# OpenBook_Schematic_v61.net
KiCad netlist of a schematic drawn in EAGLE
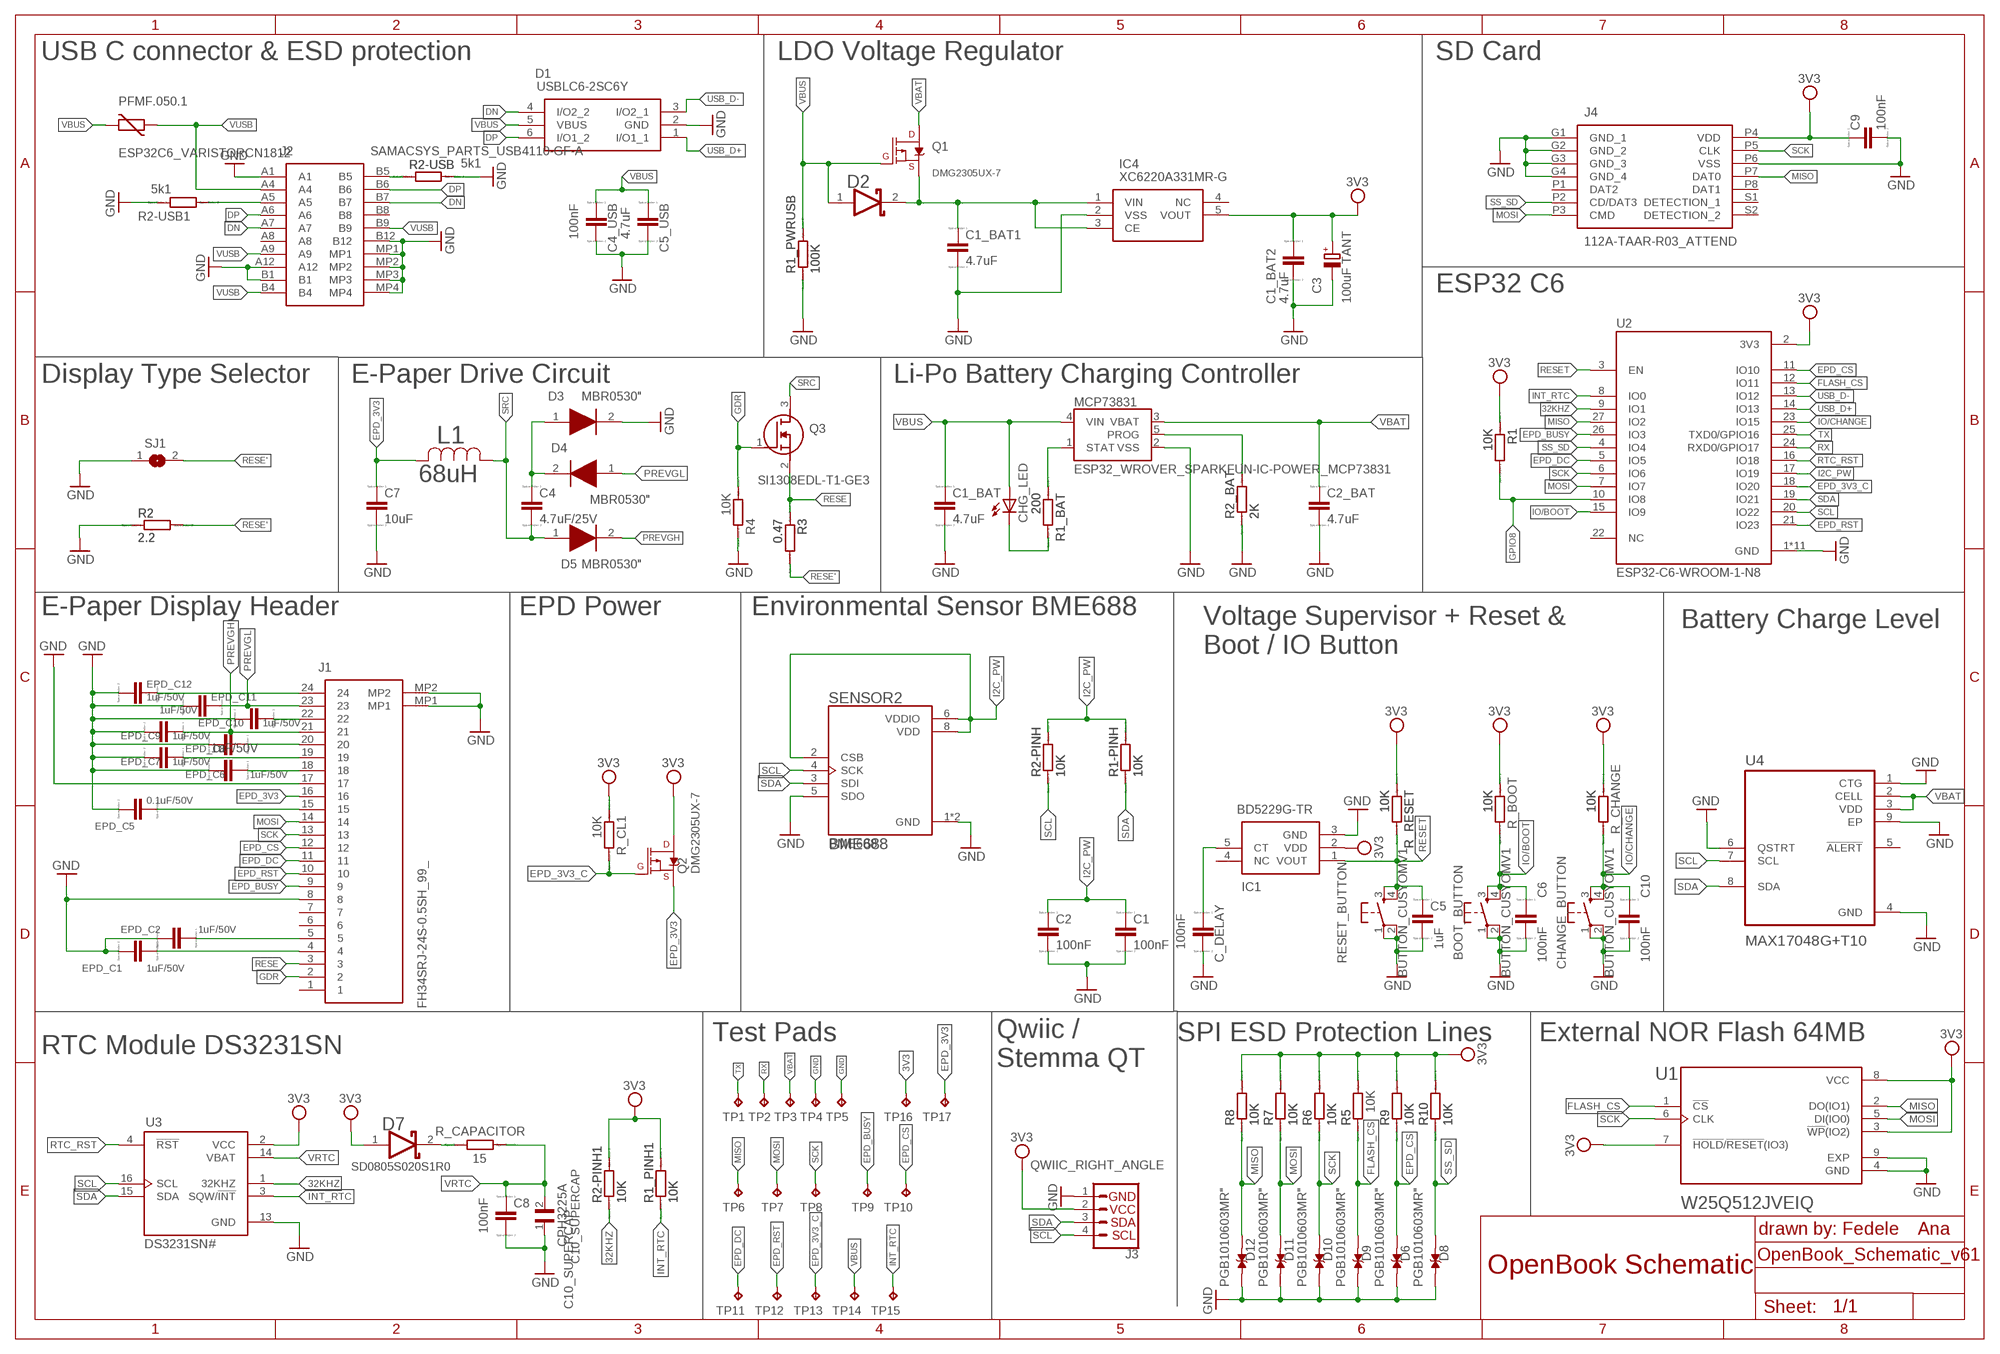
[diagram p0: schematic, sheet 1]

(export (version "E")
  (design (tool "Eeschema 10.0.6"))
  (components
    (comp (ref "BOOT_BUTTON")
      (value "BUTTON_CUSYOMV1")
      (footprint "eagle-import:MYBUTTON")
      (libsource (lib "eagle-import") (part "BUTTON_CUSYOMV1"))
    )
    (comp (ref "C1")
      (value "100nF")
      (footprint "eagle-import:ESP32_WROVER_EAGLE-LTSPICE_C0402")
      (libsource (lib "eagle-import") (part "ESP32_WROVER_EAGLE-LTSPICE_CC0402"))
    )
    (comp (ref "C1_BAT")
      (value "4.7uF")
      (footprint "eagle-import:ESP32_WROVER_EAGLE-LTSPICE_C0402")
      (libsource (lib "eagle-import") (part "ESP32_WROVER_EAGLE-LTSPICE_CC0402"))
    )
    (comp (ref "C1_BAT1")
      (value "4.7uF")
      (footprint "eagle-import:ESP32_WROVER_EAGLE-LTSPICE_C0402")
      (libsource (lib "eagle-import") (part "ESP32_WROVER_EAGLE-LTSPICE_CC0402"))
    )
    (comp (ref "C1_BAT2")
      (value "4.7uF")
      (footprint "eagle-import:ESP32_WROVER_EAGLE-LTSPICE_C0402")
      (libsource (lib "eagle-import") (part "ESP32_WROVER_EAGLE-LTSPICE_CC0402"))
    )
    (comp (ref "C2")
      (value "100nF")
      (footprint "eagle-import:ESP32_WROVER_EAGLE-LTSPICE_C0402")
      (libsource (lib "eagle-import") (part "ESP32_WROVER_EAGLE-LTSPICE_CC0402"))
    )
    (comp (ref "C2_BAT")
      (value "4.7uF")
      (footprint "eagle-import:ESP32_WROVER_EAGLE-LTSPICE_C0402")
      (libsource (lib "eagle-import") (part "ESP32_WROVER_EAGLE-LTSPICE_CC0402"))
    )
    (comp (ref "C3")
      (value "100uF TANT")
      (footprint "eagle-import:RCL_CT3528")
      (libsource (lib "eagle-import") (part "RCL_CPOL-EUCT3528"))
    )
    (comp (ref "C4")
      (value "4.7uF/25V")
      (footprint "eagle-import:ESP32_WROVER_EAGLE-LTSPICE_C0402")
      (libsource (lib "eagle-import") (part "ESP32_WROVER_EAGLE-LTSPICE_CC0402"))
    )
    (comp (ref "C4_USB")
      (value "100nF")
      (footprint "eagle-import:ESP32_WROVER_EAGLE-LTSPICE_C0402")
      (libsource (lib "eagle-import") (part "ESP32_WROVER_EAGLE-LTSPICE_CC0402"))
    )
    (comp (ref "C5")
      (value "1uF")
      (footprint "eagle-import:ESP32_WROVER_EAGLE-LTSPICE_C0402")
      (libsource (lib "eagle-import") (part "ESP32_WROVER_EAGLE-LTSPICE_CC0402"))
    )
    (comp (ref "C5_USB")
      (value "4.7uF")
      (footprint "eagle-import:ESP32_WROVER_EAGLE-LTSPICE_C0402")
      (libsource (lib "eagle-import") (part "ESP32_WROVER_EAGLE-LTSPICE_CC0402"))
    )
    (comp (ref "C6")
      (value "100nF")
      (footprint "eagle-import:ESP32_WROVER_EAGLE-LTSPICE_C0402")
      (libsource (lib "eagle-import") (part "ESP32_WROVER_EAGLE-LTSPICE_CC0402"))
    )
    (comp (ref "C7")
      (value "10uF")
      (footprint "eagle-import:ESP32_WROVER_EAGLE-LTSPICE_C0402")
      (libsource (lib "eagle-import") (part "ESP32_WROVER_EAGLE-LTSPICE_CC0402"))
    )
    (comp (ref "C8")
      (value "100nF")
      (footprint "eagle-import:ESP32_WROVER_EAGLE-LTSPICE_C0402")
      (libsource (lib "eagle-import") (part "ESP32_WROVER_EAGLE-LTSPICE_CC0402"))
    )
    (comp (ref "C9")
      (value "100nF")
      (footprint "eagle-import:ESP32_WROVER_EAGLE-LTSPICE_C0402")
      (libsource (lib "eagle-import") (part "ESP32_WROVER_EAGLE-LTSPICE_CC0402"))
    )
    (comp (ref "C10")
      (value "100nF")
      (footprint "eagle-import:ESP32_WROVER_EAGLE-LTSPICE_C0402")
      (libsource (lib "eagle-import") (part "ESP32_WROVER_EAGLE-LTSPICE_CC0402"))
    )
    (comp (ref "C10_SUPERCAP")
      (value "CPH3225A")
      (footprint "eagle-import:CAPCP3225X100N")
      (fields (field (name "MF") "Seiko Instruments"))
      (libsource (lib "eagle-import") (part "CPH3225A"))
    )
    (comp (ref "CHANGE_BUTTON")
      (value "BUTTON_CUSYOMV1")
      (footprint "eagle-import:MYBUTTON")
      (libsource (lib "eagle-import") (part "BUTTON_CUSYOMV1"))
    )
    (comp (ref "CHG_LED")
      (value "ADAFRUIT_LEDCHIP-LED0603")
      (footprint "eagle-import:ADAFRUIT_CHIP-LED0603")
      (libsource (lib "eagle-import") (part "ADAFRUIT_LEDCHIP-LED0603"))
    )
    (comp (ref "C_DELAY")
      (value "100nF")
      (footprint "eagle-import:ESP32_WROVER_EAGLE-LTSPICE_C0402")
      (libsource (lib "eagle-import") (part "ESP32_WROVER_EAGLE-LTSPICE_CC0402"))
    )
    (comp (ref "D1")
      (value "USBLC6-2SC6Y")
      (footprint "eagle-import:SOT95P280X145-6N")
      (fields (field (name "MF") "STMicroelectronics"))
      (libsource (lib "eagle-import") (part "USBLC6-2SC6Y"))
    )
    (comp (ref "D2")
      (value "ESP32_WROVER_AVX---SD0805S020S1R0_AVX_SD0805S020S1R0_0_0AVX_SD0805S020S1R0_0_0")
      (footprint "eagle-import:ESP32_WROVER_AVX---SD0805S020S1R0_AVX_SD0805S020S1R0_0")
      (libsource (lib "eagle-import") (part "ESP32_WROVER_AVX---SD0805S020S1R0_AVX_SD0805S020S1R0_0_0AVX_SD0805S020S1R0_0_0"))
    )
    (comp (ref "D3")
      (value "MBR0530\"")
      (footprint "eagle-import:SOD3716X135N")
      (libsource (lib "eagle-import") (part "MBR0530{dblquote}"))
    )
    (comp (ref "D4")
      (value "MBR0530\"")
      (footprint "eagle-import:SOD3716X135N")
      (libsource (lib "eagle-import") (part "MBR0530{dblquote}"))
    )
    (comp (ref "D5")
      (value "MBR0530\"")
      (footprint "eagle-import:SOD3716X135N")
      (libsource (lib "eagle-import") (part "MBR0530{dblquote}"))
    )
    (comp (ref "D6")
      (value "PGB1010603MR\"")
      (footprint "eagle-import:DIOC1608X36N")
      (libsource (lib "eagle-import") (part "PGB1010603MR{dblquote}"))
    )
    (comp (ref "D7")
      (value "SD0805S020S1R0")
      (footprint "eagle-import:ESP32_WROVER_AVX---SD0805S020S1R0_AVX_SD0805S020S1R0_0")
      (libsource (lib "eagle-import") (part "ESP32_WROVER_AVX---SD0805S020S1R0_AVX_SD0805S020S1R0_0_0AVX_SD0805S020S1R0_0_0"))
    )
    (comp (ref "D8")
      (value "PGB1010603MR\"")
      (footprint "eagle-import:DIOC1608X36N")
      (libsource (lib "eagle-import") (part "PGB1010603MR{dblquote}"))
    )
    (comp (ref "D9")
      (value "PGB1010603MR\"")
      (footprint "eagle-import:DIOC1608X36N")
      (libsource (lib "eagle-import") (part "PGB1010603MR{dblquote}"))
    )
    (comp (ref "D10")
      (value "PGB1010603MR\"")
      (footprint "eagle-import:DIOC1608X36N")
      (libsource (lib "eagle-import") (part "PGB1010603MR{dblquote}"))
    )
    (comp (ref "D11")
      (value "PGB1010603MR\"")
      (footprint "eagle-import:DIOC1608X36N")
      (libsource (lib "eagle-import") (part "PGB1010603MR{dblquote}"))
    )
    (comp (ref "D12")
      (value "PGB1010603MR\"")
      (footprint "eagle-import:DIOC1608X36N")
      (libsource (lib "eagle-import") (part "PGB1010603MR{dblquote}"))
    )
    (comp (ref "EPD_C1")
      (value "1uF/50V")
      (footprint "eagle-import:ESP32_WROVER_EAGLE-LTSPICE_C0402")
      (libsource (lib "eagle-import") (part "ESP32_WROVER_EAGLE-LTSPICE_CC0402"))
    )
    (comp (ref "EPD_C2")
      (value "1uF/50V")
      (footprint "eagle-import:ESP32_WROVER_EAGLE-LTSPICE_C0402")
      (libsource (lib "eagle-import") (part "ESP32_WROVER_EAGLE-LTSPICE_CC0402"))
    )
    (comp (ref "EPD_C5")
      (value "0.1uF/50V")
      (footprint "eagle-import:ESP32_WROVER_EAGLE-LTSPICE_C0402")
      (libsource (lib "eagle-import") (part "ESP32_WROVER_EAGLE-LTSPICE_CC0402"))
    )
    (comp (ref "EPD_C6")
      (value "1uF/50V")
      (footprint "eagle-import:ESP32_WROVER_EAGLE-LTSPICE_C0402")
      (libsource (lib "eagle-import") (part "ESP32_WROVER_EAGLE-LTSPICE_CC0402"))
    )
    (comp (ref "EPD_C7")
      (value "1uF/50V")
      (footprint "eagle-import:ESP32_WROVER_EAGLE-LTSPICE_C0402")
      (libsource (lib "eagle-import") (part "ESP32_WROVER_EAGLE-LTSPICE_CC0402"))
    )
    (comp (ref "EPD_C8")
      (value "1uF/50V")
      (footprint "eagle-import:ESP32_WROVER_EAGLE-LTSPICE_C0402")
      (libsource (lib "eagle-import") (part "ESP32_WROVER_EAGLE-LTSPICE_CC0402"))
    )
    (comp (ref "EPD_C9")
      (value "1uF/50V")
      (footprint "eagle-import:ESP32_WROVER_EAGLE-LTSPICE_C0402")
      (libsource (lib "eagle-import") (part "ESP32_WROVER_EAGLE-LTSPICE_CC0402"))
    )
    (comp (ref "EPD_C10")
      (value "1uF/50V")
      (footprint "eagle-import:ESP32_WROVER_EAGLE-LTSPICE_C0402")
      (libsource (lib "eagle-import") (part "ESP32_WROVER_EAGLE-LTSPICE_CC0402"))
    )
    (comp (ref "EPD_C11")
      (value "1uF/50V")
      (footprint "eagle-import:ESP32_WROVER_EAGLE-LTSPICE_C0402")
      (libsource (lib "eagle-import") (part "ESP32_WROVER_EAGLE-LTSPICE_CC0402"))
    )
    (comp (ref "EPD_C12")
      (value "1uF/50V")
      (footprint "eagle-import:ESP32_WROVER_EAGLE-LTSPICE_C0402")
      (libsource (lib "eagle-import") (part "ESP32_WROVER_EAGLE-LTSPICE_CC0402"))
    )
    (comp (ref "IC1")
      (value "BD5229G-TR")
      (footprint "eagle-import:SOT95P280X125-5N")
      (fields (field (name "MOUSER_PART_NUMBER") "755-BD5229G-TR"))
      (libsource (lib "eagle-import") (part "BD5229G-TR"))
    )
    (comp (ref "IC4")
      (value "XC6220A331MR-G")
      (footprint "eagle-import:SOT95P280X120-5N")
      (fields (field (name "MOUSER_PART_NUMBER") "865-XC6220A331MR-G"))
      (libsource (lib "eagle-import") (part "XC6220A331MR-G"))
    )
    (comp (ref "J1")
      (value "FH34SRJ-24S-0.5SH_99_")
      (footprint "eagle-import:FH34SRJ24S05SH99")
      (fields
        (field (name "MANUFACTURER_PART_NUMBER") "FH34SRJ-24S-0.5SH(99)")
        (field (name "MOUSER_PART_NUMBER") "798-FH34SRJ24S05SH99")
      )
      (libsource (lib "eagle-import") (part "FH34SRJ-24S-0.5SH_99_"))
    )
    (comp (ref "J2")
      (value "SAMACSYS_PARTS_USB4110-GF-A")
      (footprint "eagle-import:SAMACSYS_PARTS_USB4110GFA")
      (fields
        (field (name "MANUFACTURER_PART_NUMBER") "USB4110-GF-A")
        (field (name "MOUSER_PART_NUMBER") "640-USB4110-GF-A")
      )
      (libsource (lib "eagle-import") (part "SAMACSYS_PARTS_USB4110-GF-A"))
    )
    (comp (ref "J3")
      (value "QWIIC_RIGHT_ANGLE")
      (footprint "eagle-import:JST04_1MM_RA")
      (libsource (lib "eagle-import") (part "QWIIC_CONNECTORJS-1MM"))
    )
    (comp (ref "J4")
      (value "112A-TAAR-R03_ATTEND")
      (footprint "eagle-import:112ATAARR03ATTEND")
      (fields (field (name "MANUFACTURER_PART_NUMBER") "112A-TAAR-R03 ATTEND"))
      (libsource (lib "eagle-import") (part "112A-TAAR-R03_ATTEND"))
    )
    (comp (ref "L1")
      (value "68uH")
      (footprint "eagle-import:IND_4828-WE-TPC_WRE")
      (fields
        (field (name "MANUFACTURER_PART_NUMBER") "744043680")
        (field (name "COPYRIGHT") "Copyright (C) 2024 Ultra Librarian. All rights reserved.")
      )
      (libsource (lib "eagle-import") (part "744043680IND_4828-WE-TPC_WRE"))
    )
    (comp (ref "MCP73831")
      (value "ESP32_WROVER_SPARKFUN-IC-POWER_MCP73831")
      (footprint "eagle-import:ESP32_WROVER_SPARKFUN-IC-POWER_SOT23-5")
      (libsource (lib "eagle-import") (part "ESP32_WROVER_SPARKFUN-IC-POWER_MCP73831"))
    )
    (comp (ref "PFMF.050.1")
      (value "ESP32C6_VARISTORCN1812")
      (footprint "eagle-import:ESP32C6_VARISTOR_CT_CN1812")
      (libsource (lib "eagle-import") (part "ESP32C6_VARISTORCN1812"))
    )
    (comp (ref "Q1")
      (value "20V/4.2A/52mΩ/1.4W")
      (footprint "eagle-import:ESP32_WROVER_SPARKFUN-DISCRETESEMI_SOT23-3")
      (libsource (lib "eagle-import") (part "ESP32_WROVER_SPARKFUN-DISCRETESEMI_MOSFET_PCH-DMG2305UX-7"))
    )
    (comp (ref "Q2")
      (value "20V/4.2A/52mΩ/1.4W")
      (footprint "eagle-import:ESP32_WROVER_SPARKFUN-DISCRETESEMI_SOT23-3")
      (libsource (lib "eagle-import") (part "ESP32_WROVER_SPARKFUN-DISCRETESEMI_MOSFET_PCH-DMG2305UX-7"))
    )
    (comp (ref "Q3")
      (value "SI1308EDL-T1-GE3")
      (footprint "eagle-import:SOT65P210X110-3N")
      (fields (field (name "MF") "Vishay Siliconix"))
      (libsource (lib "eagle-import") (part "SI1308EDL-T1-GE3"))
    )
    (comp (ref "R1")
      (value "10K")
      (footprint "eagle-import:ESP32_WROVER_EAGLE-LTSPICE_R0402")
      (libsource (lib "eagle-import") (part "ESP32_WROVER_EAGLE-LTSPICE_RR0402"))
    )
    (comp (ref "R1-PINH")
      (value "10K")
      (footprint "eagle-import:ESP32_WROVER_EAGLE-LTSPICE_R0402")
      (libsource (lib "eagle-import") (part "ESP32_WROVER_EAGLE-LTSPICE_RR0402"))
    )
    (comp (ref "R1_BAT")
      (value "200")
      (footprint "eagle-import:ESP32_WROVER_EAGLE-LTSPICE_R0402")
      (libsource (lib "eagle-import") (part "ESP32_WROVER_EAGLE-LTSPICE_RR0402"))
    )
    (comp (ref "R1_PINH1")
      (value "10K")
      (footprint "eagle-import:ESP32_WROVER_EAGLE-LTSPICE_R0402")
      (libsource (lib "eagle-import") (part "ESP32_WROVER_EAGLE-LTSPICE_RR0402"))
    )
    (comp (ref "R1_PWRUSB")
      (value "100K")
      (footprint "eagle-import:ESP32_WROVER_EAGLE-LTSPICE_R0402")
      (libsource (lib "eagle-import") (part "ESP32_WROVER_EAGLE-LTSPICE_RR0402"))
    )
    (comp (ref "R2")
      (value "2.2")
      (footprint "eagle-import:ESP32_WROVER_EAGLE-LTSPICE_R0402")
      (libsource (lib "eagle-import") (part "ESP32_WROVER_EAGLE-LTSPICE_RR0402"))
    )
    (comp (ref "R2-PINH")
      (value "10K")
      (footprint "eagle-import:ESP32_WROVER_EAGLE-LTSPICE_R0402")
      (libsource (lib "eagle-import") (part "ESP32_WROVER_EAGLE-LTSPICE_RR0402"))
    )
    (comp (ref "R2-PINH1")
      (value "10K")
      (footprint "eagle-import:ESP32_WROVER_EAGLE-LTSPICE_R0402")
      (libsource (lib "eagle-import") (part "ESP32_WROVER_EAGLE-LTSPICE_RR0402"))
    )
    (comp (ref "R2-USB")
      (value "5k1")
      (footprint "eagle-import:ESP32_WROVER_EAGLE-LTSPICE_R0402")
      (libsource (lib "eagle-import") (part "ESP32_WROVER_EAGLE-LTSPICE_RR0402"))
    )
    (comp (ref "R2-USB1")
      (value "5k1")
      (footprint "eagle-import:ESP32_WROVER_EAGLE-LTSPICE_R0402")
      (libsource (lib "eagle-import") (part "ESP32_WROVER_EAGLE-LTSPICE_RR0402"))
    )
    (comp (ref "R2_BAT")
      (value "2K")
      (footprint "eagle-import:ESP32_WROVER_EAGLE-LTSPICE_R0402")
      (libsource (lib "eagle-import") (part "ESP32_WROVER_EAGLE-LTSPICE_RR0402"))
    )
    (comp (ref "R3")
      (value "0.47")
      (footprint "eagle-import:ESP32_WROVER_EAGLE-LTSPICE_R0402")
      (libsource (lib "eagle-import") (part "ESP32_WROVER_EAGLE-LTSPICE_RR0402"))
    )
    (comp (ref "R4")
      (value "10K")
      (footprint "eagle-import:ESP32_WROVER_EAGLE-LTSPICE_R0402")
      (libsource (lib "eagle-import") (part "ESP32_WROVER_EAGLE-LTSPICE_RR0402"))
    )
    (comp (ref "R5")
      (value "10K")
      (footprint "eagle-import:ESP32_WROVER_EAGLE-LTSPICE_R0402")
      (libsource (lib "eagle-import") (part "ESP32_WROVER_EAGLE-LTSPICE_RR0402"))
    )
    (comp (ref "R6")
      (value "10K")
      (footprint "eagle-import:ESP32_WROVER_EAGLE-LTSPICE_R0402")
      (libsource (lib "eagle-import") (part "ESP32_WROVER_EAGLE-LTSPICE_RR0402"))
    )
    (comp (ref "R7")
      (value "10K")
      (footprint "eagle-import:ESP32_WROVER_EAGLE-LTSPICE_R0402")
      (libsource (lib "eagle-import") (part "ESP32_WROVER_EAGLE-LTSPICE_RR0402"))
    )
    (comp (ref "R8")
      (value "10K")
      (footprint "eagle-import:ESP32_WROVER_EAGLE-LTSPICE_R0402")
      (libsource (lib "eagle-import") (part "ESP32_WROVER_EAGLE-LTSPICE_RR0402"))
    )
    (comp (ref "R9")
      (value "10K")
      (footprint "eagle-import:ESP32_WROVER_EAGLE-LTSPICE_R0402")
      (libsource (lib "eagle-import") (part "ESP32_WROVER_EAGLE-LTSPICE_RR0402"))
    )
    (comp (ref "R10")
      (value "10K")
      (footprint "eagle-import:ESP32_WROVER_EAGLE-LTSPICE_R0402")
      (libsource (lib "eagle-import") (part "ESP32_WROVER_EAGLE-LTSPICE_RR0402"))
    )
    (comp (ref "RESET_BUTTON")
      (value "BUTTON_CUSYOMV1")
      (footprint "eagle-import:MYBUTTON")
      (libsource (lib "eagle-import") (part "BUTTON_CUSYOMV1"))
    )
    (comp (ref "R_BOOT")
      (value "10K")
      (footprint "eagle-import:ESP32_WROVER_EAGLE-LTSPICE_R0402")
      (libsource (lib "eagle-import") (part "ESP32_WROVER_EAGLE-LTSPICE_RR0402"))
    )
    (comp (ref "R_CAPACITOR")
      (value "15")
      (footprint "eagle-import:ESP32_WROVER_EAGLE-LTSPICE_R0402")
      (libsource (lib "eagle-import") (part "ESP32_WROVER_EAGLE-LTSPICE_RR0402"))
    )
    (comp (ref "R_CHANGE")
      (value "10K")
      (footprint "eagle-import:ESP32_WROVER_EAGLE-LTSPICE_R0402")
      (libsource (lib "eagle-import") (part "ESP32_WROVER_EAGLE-LTSPICE_RR0402"))
    )
    (comp (ref "R_CL1")
      (value "10K")
      (footprint "eagle-import:ESP32_WROVER_EAGLE-LTSPICE_R0402")
      (libsource (lib "eagle-import") (part "ESP32_WROVER_EAGLE-LTSPICE_RR0402"))
    )
    (comp (ref "R_RESET")
      (value "10K")
      (footprint "eagle-import:ESP32_WROVER_EAGLE-LTSPICE_R0402")
      (libsource (lib "eagle-import") (part "ESP32_WROVER_EAGLE-LTSPICE_RR0402"))
    )
    (comp (ref "SENSOR2")
      (value "BME688")
      (footprint "eagle-import:ESP32_WROVER_BME680_PSON80P300X300X100-8N")
      (fields (field (name "MF") "Bosch Sensortec") (field (name "MP") "BME680"))
      (libsource (lib "eagle-import") (part "ESP32_WROVER_BME680_BME680"))
    )
    (comp (ref "SJ1") (value "SJ") (footprint "eagle-import:SJ") (libsource (lib "eagle-import") (part "SJ")))
    (comp (ref "TP1")
      (value "TPTP20R")
      (footprint "eagle-import:TP20R")
      (libsource (lib "eagle-import") (part "TPTP20R"))
    )
    (comp (ref "TP2")
      (value "TPTP20R")
      (footprint "eagle-import:TP20R")
      (libsource (lib "eagle-import") (part "TPTP20R"))
    )
    (comp (ref "TP3")
      (value "TPTP20R")
      (footprint "eagle-import:TP20R")
      (libsource (lib "eagle-import") (part "TPTP20R"))
    )
    (comp (ref "TP4")
      (value "TPTP20R")
      (footprint "eagle-import:TP20R")
      (libsource (lib "eagle-import") (part "TPTP20R"))
    )
    (comp (ref "TP5")
      (value "TPTP20R")
      (footprint "eagle-import:TP20R")
      (libsource (lib "eagle-import") (part "TPTP20R"))
    )
    (comp (ref "TP6")
      (value "TPTP20R")
      (footprint "eagle-import:TP20R")
      (libsource (lib "eagle-import") (part "TPTP20R"))
    )
    (comp (ref "TP7")
      (value "TPTP20R")
      (footprint "eagle-import:TP20R")
      (fields (field (name "SPICEPREFIX") "X"))
      (libsource (lib "eagle-import") (part "TPTP20R"))
    )
    (comp (ref "TP8")
      (value "TPTP20R")
      (footprint "eagle-import:TP20R")
      (libsource (lib "eagle-import") (part "TPTP20R"))
    )
    (comp (ref "TP9")
      (value "TPTP20R")
      (footprint "eagle-import:TP20R")
      (libsource (lib "eagle-import") (part "TPTP20R"))
    )
    (comp (ref "TP10")
      (value "TPTP20R")
      (footprint "eagle-import:TP20R")
      (libsource (lib "eagle-import") (part "TPTP20R"))
    )
    (comp (ref "TP11")
      (value "TPTP20R")
      (footprint "eagle-import:TP20R")
      (libsource (lib "eagle-import") (part "TPTP20R"))
    )
    (comp (ref "TP12")
      (value "TPTP20R")
      (footprint "eagle-import:TP20R")
      (libsource (lib "eagle-import") (part "TPTP20R"))
    )
    (comp (ref "TP13")
      (value "TPTP20R")
      (footprint "eagle-import:TP20R")
      (libsource (lib "eagle-import") (part "TPTP20R"))
    )
    (comp (ref "TP14")
      (value "TPTP20R")
      (footprint "eagle-import:TP20R")
      (libsource (lib "eagle-import") (part "TPTP20R"))
    )
    (comp (ref "TP15")
      (value "TPTP20R")
      (footprint "eagle-import:TP20R")
      (libsource (lib "eagle-import") (part "TPTP20R"))
    )
    (comp (ref "TP16")
      (value "TPTP20R")
      (footprint "eagle-import:TP20R")
      (libsource (lib "eagle-import") (part "TPTP20R"))
    )
    (comp (ref "TP17")
      (value "TPTP20R")
      (footprint "eagle-import:TP20R")
      (libsource (lib "eagle-import") (part "TPTP20R"))
    )
    (comp (ref "U1")
      (value "W25Q512JVEIQ")
      (footprint "eagle-import:SON127P600X800X80-9N")
      (fields (field (name "MF") "Winbond Electronics"))
      (libsource (lib "eagle-import") (part "W25Q512JVEIQ"))
    )
    (comp (ref "U2")
      (value "ESP32-C6-WROOM-1-N8")
      (footprint "eagle-import:XCVR_ESP32-C6-WROOM-1-N8")
      (fields (field (name "MF") "Espressif Systems"))
      (libsource (lib "eagle-import") (part "ESP32-C6-WROOM-1-N8"))
    )
    (comp (ref "U3")
      (value "DS3231SN#")
      (footprint "eagle-import:SOIC127P1032X265-16N")
      (fields (field (name "MF") "Analog Devices"))
      (libsource (lib "eagle-import") (part "DS3231SN#"))
    )
    (comp (ref "U4")
      (value "MAX17048G+T10")
      (footprint "eagle-import:SON50P200X200X80-9N")
      (fields (field (name "MF") "Analog Devices"))
      (libsource (lib "eagle-import") (part "MAX17048G+T10"))
    )
  )
  (nets
    (net (code "1") (name "3V3") (class "Default")
      (node (ref "C1_BAT2") (pin "1") (pinfunction "1_1") (pintype "passive"))
      (node (ref "C3") (pin "+") (pinfunction "+_+") (pintype "passive"))
      (node (ref "C9") (pin "1") (pinfunction "1_1") (pintype "passive"))
      (node (ref "D7") (pin "1") (pinfunction "ANODE_1") (pintype "bidirectional"))
      (node (ref "IC1") (pin "2") (pinfunction "VDD_2") (pintype "bidirectional"))
      (node (ref "IC4") (pin "5") (pinfunction "VOUT_5") (pintype "bidirectional"))
      (node (ref "J3") (pin "2") (pinfunction "2_2") (pintype "power_in"))
      (node (ref "J4") (pin "P4") (pinfunction "VDD_P4") (pintype "bidirectional"))
      (node (ref "Q2") (pin "1") (pinfunction "D_1") (pintype "bidirectional"))
      (node (ref "R1") (pin "1") (pinfunction "1_1") (pintype "passive"))
      (node (ref "R10") (pin "2") (pinfunction "2_2") (pintype "passive"))
      (node (ref "R1_PINH1") (pin "2") (pinfunction "2_2") (pintype "passive"))
      (node (ref "R2-PINH1") (pin "2") (pinfunction "2_2") (pintype "passive"))
      (node (ref "R5") (pin "2") (pinfunction "2_2") (pintype "passive"))
      (node (ref "R6") (pin "2") (pinfunction "2_2") (pintype "passive"))
      (node (ref "R7") (pin "2") (pinfunction "2_2") (pintype "passive"))
      (node (ref "R8") (pin "2") (pinfunction "2_2") (pintype "passive"))
      (node (ref "R9") (pin "2") (pinfunction "2_2") (pintype "passive"))
      (node (ref "R_BOOT") (pin "1") (pinfunction "1_1") (pintype "passive"))
      (node (ref "R_CHANGE") (pin "1") (pinfunction "1_1") (pintype "passive"))
      (node (ref "R_CL1") (pin "1") (pinfunction "1_1") (pintype "passive"))
      (node (ref "R_RESET") (pin "1") (pinfunction "1_1") (pintype "passive"))
      (node (ref "TP16") (pin "TP") (pinfunction "TP_TP") (pintype "input"))
      (node (ref "U1") (pin "3") (pinfunction "~{WP}(IO2)_3") (pintype "bidirectional"))
      (node (ref "U1") (pin "7") (pinfunction "~{HOLD}/~{RESET}(IO3)_7") (pintype "bidirectional"))
      (node (ref "U1") (pin "8") (pinfunction "VCC_8") (pintype "power_in"))
      (node (ref "U2") (pin "2") (pinfunction "3V3_2") (pintype "power_in"))
      (node (ref "U3") (pin "2") (pinfunction "VCC_2") (pintype "power_in"))
    )
    (net (code "2") (name "32KHZ") (class "Default")
      (node (ref "R2-PINH1") (pin "1") (pinfunction "1_1") (pintype "passive"))
      (node (ref "U2") (pin "9") (pinfunction "IO1_9") (pintype "bidirectional"))
      (node (ref "U3") (pin "1") (pinfunction "32KHZ_1") (pintype "output"))
    )
    (net (code "3") (name "DN") (class "Default")
      (node (ref "D1") (pin "4") (pinfunction "I/O2_2_4") (pintype "bidirectional"))
      (node (ref "J2") (pin "A7") (pinfunction "A7_A7") (pintype "bidirectional"))
      (node (ref "J2") (pin "B7") (pinfunction "B7_B7") (pintype "bidirectional"))
    )
    (net (code "4") (name "DP") (class "Default")
      (node (ref "D1") (pin "6") (pinfunction "I/O1_2_6") (pintype "bidirectional"))
      (node (ref "J2") (pin "A6") (pinfunction "A6_A6") (pintype "bidirectional"))
      (node (ref "J2") (pin "B6") (pinfunction "B6_B6") (pintype "bidirectional"))
    )
    (net (code "5") (name "EPD_3V3") (class "Default")
      (node (ref "C7") (pin "1") (pinfunction "1_1") (pintype "passive"))
      (node (ref "J1") (pin "16") (pinfunction "16_16") (pintype "bidirectional"))
      (node (ref "L1") (pin "2") (pinfunction "2_2") (pintype "passive"))
      (node (ref "Q2") (pin "3") (pinfunction "S_3") (pintype "bidirectional"))
      (node (ref "TP17") (pin "TP") (pinfunction "TP_TP") (pintype "input"))
    )
    (net (code "6") (name "EPD_3V3_C") (class "Default")
      (node (ref "Q2") (pin "2") (pinfunction "G_2") (pintype "bidirectional"))
      (node (ref "R_CL1") (pin "2") (pinfunction "2_2") (pintype "passive"))
      (node (ref "TP13") (pin "TP") (pinfunction "TP_TP") (pintype "input"))
      (node (ref "U2") (pin "18") (pinfunction "IO20_18") (pintype "bidirectional"))
    )
    (net (code "7") (name "EPD_BUSY") (class "Default")
      (node (ref "J1") (pin "9") (pinfunction "9_9") (pintype "bidirectional"))
      (node (ref "TP9") (pin "TP") (pinfunction "TP_TP") (pintype "input"))
      (node (ref "U2") (pin "26") (pinfunction "IO3_26") (pintype "bidirectional"))
    )
    (net (code "8") (name "EPD_CS") (class "Default")
      (node (ref "D6") (pin "2") (pinfunction "2_2") (pintype "passive"))
      (node (ref "J1") (pin "12") (pinfunction "12_12") (pintype "bidirectional"))
      (node (ref "R9") (pin "1") (pinfunction "1_1") (pintype "passive"))
      (node (ref "TP10") (pin "TP") (pinfunction "TP_TP") (pintype "input"))
      (node (ref "U2") (pin "11") (pinfunction "IO10_11") (pintype "bidirectional"))
    )
    (net (code "9") (name "EPD_DC") (class "Default")
      (node (ref "J1") (pin "11") (pinfunction "11_11") (pintype "bidirectional"))
      (node (ref "TP11") (pin "TP") (pinfunction "TP_TP") (pintype "input"))
      (node (ref "U2") (pin "5") (pinfunction "IO5_5") (pintype "bidirectional"))
    )
    (net (code "10") (name "EPD_RST") (class "Default")
      (node (ref "J1") (pin "10") (pinfunction "10_10") (pintype "bidirectional"))
      (node (ref "TP12") (pin "TP") (pinfunction "TP_TP") (pintype "input"))
      (node (ref "U2") (pin "21") (pinfunction "IO23_21") (pintype "bidirectional"))
    )
    (net (code "11") (name "FLASH_CS") (class "Default")
      (node (ref "D9") (pin "2") (pinfunction "2_2") (pintype "passive"))
      (node (ref "R5") (pin "1") (pinfunction "1_1") (pintype "passive"))
      (node (ref "U1") (pin "1") (pinfunction "~{CS}_1") (pintype "input"))
      (node (ref "U2") (pin "12") (pinfunction "IO11_12") (pintype "bidirectional"))
    )
    (net (code "12") (name "GDR") (class "Default")
      (node (ref "J1") (pin "2") (pinfunction "2_2") (pintype "bidirectional"))
      (node (ref "Q3") (pin "1") (pinfunction "G_1") (pintype "bidirectional"))
      (node (ref "R4") (pin "1") (pinfunction "1_1") (pintype "passive"))
    )
    (net (code "13") (name "GND") (class "Default")
      (node (ref "BOOT_BUTTON") (pin "1") (pinfunction "1_1") (pintype "passive"))
      (node (ref "BOOT_BUTTON") (pin "2") (pinfunction "2_2") (pintype "passive"))
      (node (ref "C1") (pin "2") (pinfunction "2_2") (pintype "passive"))
      (node (ref "C10") (pin "2") (pinfunction "2_2") (pintype "passive"))
      (node (ref "C10_SUPERCAP") (pin "1") (pinfunction "1_1") (pintype "passive"))
      (node (ref "C1_BAT") (pin "2") (pinfunction "2_2") (pintype "passive"))
      (node (ref "C1_BAT1") (pin "2") (pinfunction "2_2") (pintype "passive"))
      (node (ref "C1_BAT2") (pin "2") (pinfunction "2_2") (pintype "passive"))
      (node (ref "C2") (pin "2") (pinfunction "2_2") (pintype "passive"))
      (node (ref "C2_BAT") (pin "2") (pinfunction "2_2") (pintype "passive"))
      (node (ref "C3") (pin "-") (pinfunction "-_-") (pintype "passive"))
      (node (ref "C4_USB") (pin "2") (pinfunction "2_2") (pintype "passive"))
      (node (ref "C5") (pin "2") (pinfunction "2_2") (pintype "passive"))
      (node (ref "C5_USB") (pin "2") (pinfunction "2_2") (pintype "passive"))
      (node (ref "C6") (pin "2") (pinfunction "2_2") (pintype "passive"))
      (node (ref "C7") (pin "2") (pinfunction "2_2") (pintype "passive"))
      (node (ref "C8") (pin "2") (pinfunction "2_2") (pintype "passive"))
      (node (ref "C9") (pin "2") (pinfunction "2_2") (pintype "passive"))
      (node (ref "CHANGE_BUTTON") (pin "1") (pinfunction "1_1") (pintype "passive"))
      (node (ref "CHANGE_BUTTON") (pin "2") (pinfunction "2_2") (pintype "passive"))
      (node (ref "C_DELAY") (pin "2") (pinfunction "2_2") (pintype "passive"))
      (node (ref "D1") (pin "2") (pinfunction "GND_2") (pintype "bidirectional"))
      (node (ref "D10") (pin "1") (pinfunction "1_1") (pintype "passive"))
      (node (ref "D11") (pin "1") (pinfunction "1_1") (pintype "passive"))
      (node (ref "D12") (pin "1") (pinfunction "1_1") (pintype "passive"))
      (node (ref "D3") (pin "2") (pinfunction "K_2") (pintype "bidirectional"))
      (node (ref "D6") (pin "1") (pinfunction "1_1") (pintype "passive"))
      (node (ref "D8") (pin "1") (pinfunction "1_1") (pintype "passive"))
      (node (ref "D9") (pin "1") (pinfunction "1_1") (pintype "passive"))
      (node (ref "EPD_C1") (pin "2") (pinfunction "2_2") (pintype "passive"))
      (node (ref "EPD_C10") (pin "2") (pinfunction "2_2") (pintype "passive"))
      (node (ref "EPD_C11") (pin "2") (pinfunction "2_2") (pintype "passive"))
      (node (ref "EPD_C12") (pin "2") (pinfunction "2_2") (pintype "passive"))
      (node (ref "EPD_C2") (pin "2") (pinfunction "2_2") (pintype "passive"))
      (node (ref "EPD_C5") (pin "2") (pinfunction "2_2") (pintype "passive"))
      (node (ref "EPD_C6") (pin "2") (pinfunction "2_2") (pintype "passive"))
      (node (ref "EPD_C7") (pin "2") (pinfunction "2_2") (pintype "passive"))
      (node (ref "EPD_C8") (pin "2") (pinfunction "2_2") (pintype "passive"))
      (node (ref "EPD_C9") (pin "2") (pinfunction "2_2") (pintype "passive"))
      (node (ref "IC1") (pin "3") (pinfunction "GND_3") (pintype "bidirectional"))
      (node (ref "IC4") (pin "2") (pinfunction "VSS_2") (pintype "bidirectional"))
      (node (ref "J1") (pin "17") (pinfunction "17_17") (pintype "bidirectional"))
      (node (ref "J1") (pin "8") (pinfunction "8_8") (pintype "bidirectional"))
      (node (ref "J1") (pin "MP1") (pinfunction "MP1_MP1") (pintype "bidirectional"))
      (node (ref "J1") (pin "MP2") (pinfunction "MP2_MP2") (pintype "bidirectional"))
      (node (ref "J2") (pin "A1") (pinfunction "A1_A1") (pintype "bidirectional"))
      (node (ref "J2") (pin "A12") (pinfunction "A12_A12") (pintype "bidirectional"))
      (node (ref "J2") (pin "B1") (pinfunction "B1_B1") (pintype "bidirectional"))
      (node (ref "J2") (pin "B12") (pinfunction "B12_B12") (pintype "bidirectional"))
      (node (ref "J2") (pin "MP1") (pinfunction "MP1_MP1") (pintype "bidirectional"))
      (node (ref "J2") (pin "MP2") (pinfunction "MP2_MP2") (pintype "bidirectional"))
      (node (ref "J2") (pin "MP3") (pinfunction "MP3_MP3") (pintype "bidirectional"))
      (node (ref "J2") (pin "MP4") (pinfunction "MP4_MP4") (pintype "bidirectional"))
      (node (ref "J3") (pin "1") (pinfunction "1_1") (pintype "power_in"))
      (node (ref "J4") (pin "G1") (pinfunction "GND_1_G1") (pintype "bidirectional"))
      (node (ref "J4") (pin "G2") (pinfunction "GND_2_G2") (pintype "bidirectional"))
      (node (ref "J4") (pin "G3") (pinfunction "GND_3_G3") (pintype "bidirectional"))
      (node (ref "J4") (pin "G4") (pinfunction "GND_4_G4") (pintype "bidirectional"))
      (node (ref "J4") (pin "P6") (pinfunction "VSS_P6") (pintype "bidirectional"))
      (node (ref "MCP73831") (pin "2") (pinfunction "VSS_2") (pintype "power_in"))
      (node (ref "R1_PWRUSB") (pin "1") (pinfunction "1_1") (pintype "passive"))
      (node (ref "R2") (pin "1") (pinfunction "1_1") (pintype "passive"))
      (node (ref "R2-USB") (pin "2") (pinfunction "2_2") (pintype "passive"))
      (node (ref "R2-USB1") (pin "1") (pinfunction "1_1") (pintype "passive"))
      (node (ref "R2_BAT") (pin "1") (pinfunction "1_1") (pintype "passive"))
      (node (ref "R4") (pin "2") (pinfunction "2_2") (pintype "passive"))
      (node (ref "RESET_BUTTON") (pin "1") (pinfunction "1_1") (pintype "passive"))
      (node (ref "RESET_BUTTON") (pin "2") (pinfunction "2_2") (pintype "passive"))
      (node (ref "SENSOR2") (pin "1") (pinfunction "GND_1") (pintype "power_in"))
      (node (ref "SENSOR2") (pin "5") (pinfunction "SDO_5") (pintype "bidirectional"))
      (node (ref "SENSOR2") (pin "7") (pinfunction "GND_7") (pintype "power_in"))
      (node (ref "SJ1") (pin "1") (pinfunction "1_1") (pintype "passive"))
      (node (ref "TP4") (pin "TP") (pinfunction "TP_TP") (pintype "input"))
      (node (ref "TP5") (pin "TP") (pinfunction "TP_TP") (pintype "input"))
      (node (ref "U1") (pin "4") (pinfunction "GND_4") (pintype "power_in"))
      (node (ref "U1") (pin "9") (pinfunction "EXP_9") (pintype "passive"))
      (node (ref "U2") (pin "1") (pinfunction "GND_1") (pintype "power_in"))
      (node (ref "U2") (pin "28") (pinfunction "GND_28") (pintype "power_in"))
      (node (ref "U2") (pin "29_1") (pinfunction "GND_29_1") (pintype "power_in"))
      (node (ref "U2") (pin "29_2") (pinfunction "GND_29_2") (pintype "power_in"))
      (node (ref "U2") (pin "29_3") (pinfunction "GND_29_3") (pintype "power_in"))
      (node (ref "U2") (pin "29_4") (pinfunction "GND_29_4") (pintype "power_in"))
      (node (ref "U2") (pin "29_5") (pinfunction "GND_29_5") (pintype "power_in"))
      (node (ref "U2") (pin "29_6") (pinfunction "GND_29_6") (pintype "power_in"))
      (node (ref "U2") (pin "29_7") (pinfunction "GND_29_7") (pintype "power_in"))
      (node (ref "U2") (pin "29_8") (pinfunction "GND_29_8") (pintype "power_in"))
      (node (ref "U2") (pin "29_9") (pinfunction "GND_29_9") (pintype "power_in"))
      (node (ref "U3") (pin "13") (pinfunction "GND_13") (pintype "power_in"))
      (node (ref "U4") (pin "1") (pinfunction "CTG_1") (pintype "power_in"))
      (node (ref "U4") (pin "4") (pinfunction "GND_4") (pintype "power_in"))
      (node (ref "U4") (pin "6") (pinfunction "QSTRT_6") (pintype "input"))
      (node (ref "U4") (pin "9") (pinfunction "EP_9") (pintype "power_in"))
    )
    (net (code "14") (name "GPIO8") (class "Default")
      (node (ref "R1") (pin "2") (pinfunction "2_2") (pintype "passive"))
      (node (ref "U2") (pin "10") (pinfunction "IO8_10") (pintype "bidirectional"))
    )
    (net (code "15") (name "I2C_PW") (class "Default")
      (node (ref "C1") (pin "1") (pinfunction "1_1") (pintype "passive"))
      (node (ref "C2") (pin "1") (pinfunction "1_1") (pintype "passive"))
      (node (ref "R1-PINH") (pin "2") (pinfunction "2_2") (pintype "passive"))
      (node (ref "R2-PINH") (pin "2") (pinfunction "2_2") (pintype "passive"))
      (node (ref "SENSOR2") (pin "2") (pinfunction "CSB_2") (pintype "input"))
      (node (ref "SENSOR2") (pin "6") (pinfunction "VDDIO_6") (pintype "power_in"))
      (node (ref "SENSOR2") (pin "8") (pinfunction "VDD_8") (pintype "power_in"))
      (node (ref "U2") (pin "17") (pinfunction "IO19_17") (pintype "bidirectional"))
    )
    (net (code "16") (name "INT_RTC") (class "Default")
      (node (ref "R1_PINH1") (pin "1") (pinfunction "1_1") (pintype "passive"))
      (node (ref "TP15") (pin "TP") (pinfunction "TP_TP") (pintype "input"))
      (node (ref "U2") (pin "8") (pinfunction "IO0_8") (pintype "bidirectional"))
      (node (ref "U3") (pin "3") (pinfunction "SQW/~{INT}_3") (pintype "output"))
    )
    (net (code "17") (name "IO{slash}BOOT") (class "Default")
      (node (ref "BOOT_BUTTON") (pin "3") (pinfunction "3_3") (pintype "passive"))
      (node (ref "BOOT_BUTTON") (pin "4") (pinfunction "4_4") (pintype "passive"))
      (node (ref "C6") (pin "1") (pinfunction "1_1") (pintype "passive"))
      (node (ref "R_BOOT") (pin "2") (pinfunction "2_2") (pintype "passive"))
      (node (ref "U2") (pin "15") (pinfunction "IO9_15") (pintype "bidirectional"))
    )
    (net (code "18") (name "IO{slash}CHANGE") (class "Default")
      (node (ref "C10") (pin "1") (pinfunction "1_1") (pintype "passive"))
      (node (ref "CHANGE_BUTTON") (pin "3") (pinfunction "3_3") (pintype "passive"))
      (node (ref "CHANGE_BUTTON") (pin "4") (pinfunction "4_4") (pintype "passive"))
      (node (ref "R_CHANGE") (pin "2") (pinfunction "2_2") (pintype "passive"))
      (node (ref "U2") (pin "23") (pinfunction "IO15_23") (pintype "bidirectional"))
    )
    (net (code "19") (name "MISO") (class "Default")
      (node (ref "D12") (pin "2") (pinfunction "2_2") (pintype "passive"))
      (node (ref "J4") (pin "P7") (pinfunction "DAT0_P7") (pintype "bidirectional"))
      (node (ref "R8") (pin "1") (pinfunction "1_1") (pintype "passive"))
      (node (ref "TP6") (pin "TP") (pinfunction "TP_TP") (pintype "input"))
      (node (ref "U1") (pin "2") (pinfunction "DO(IO1)_2") (pintype "bidirectional"))
      (node (ref "U2") (pin "27") (pinfunction "IO2_27") (pintype "bidirectional"))
    )
    (net (code "20") (name "MOSI") (class "Default")
      (node (ref "D11") (pin "2") (pinfunction "2_2") (pintype "passive"))
      (node (ref "J1") (pin "14") (pinfunction "14_14") (pintype "bidirectional"))
      (node (ref "J4") (pin "P3") (pinfunction "CMD_P3") (pintype "bidirectional"))
      (node (ref "R7") (pin "1") (pinfunction "1_1") (pintype "passive"))
      (node (ref "TP7") (pin "TP") (pinfunction "TP_TP") (pintype "input"))
      (node (ref "U1") (pin "5") (pinfunction "DI(IO0)_5") (pintype "bidirectional"))
      (node (ref "U2") (pin "7") (pinfunction "IO7_7") (pintype "bidirectional"))
    )
    (net (code "21") (name "Net-(CHG_LED-PadC)") (class "Default")
      (node (ref "CHG_LED") (pin "C") (pinfunction "C_C") (pintype "passive"))
      (node (ref "R1_BAT") (pin "2") (pinfunction "2_2") (pintype "passive"))
    )
    (net (code "22") (name "Net-(D2-CATHODE)") (class "Default")
      (node (ref "C1_BAT1") (pin "1") (pinfunction "1_1") (pintype "passive"))
      (node (ref "D2") (pin "2") (pinfunction "CATHODE_2") (pintype "bidirectional"))
      (node (ref "IC4") (pin "1") (pinfunction "VIN_1") (pintype "bidirectional"))
      (node (ref "IC4") (pin "3") (pinfunction "CE_3") (pintype "bidirectional"))
      (node (ref "Q1") (pin "3") (pinfunction "S_3") (pintype "bidirectional"))
    )
    (net (code "23") (name "Net-(D3-A)") (class "Default")
      (node (ref "C4") (pin "1") (pinfunction "1_1") (pintype "passive"))
      (node (ref "D3") (pin "1") (pinfunction "A_1") (pintype "bidirectional"))
      (node (ref "D4") (pin "2") (pinfunction "K_2") (pintype "bidirectional"))
    )
    (net (code "24") (name "Net-(D7-CATHODE)") (class "Default")
      (node (ref "D7") (pin "2") (pinfunction "CATHODE_2") (pintype "bidirectional"))
      (node (ref "R_CAPACITOR") (pin "2") (pinfunction "2_2") (pintype "passive"))
    )
    (net (code "25") (name "Net-(EPD_C1-Pad1)") (class "Default")
      (node (ref "EPD_C1") (pin "1") (pinfunction "1_1") (pintype "passive"))
      (node (ref "J1") (pin "4") (pinfunction "4_4") (pintype "bidirectional"))
    )
    (net (code "26") (name "Net-(EPD_C2-Pad1)") (class "Default")
      (node (ref "EPD_C2") (pin "1") (pinfunction "1_1") (pintype "passive"))
      (node (ref "J1") (pin "5") (pinfunction "5_5") (pintype "bidirectional"))
    )
    (net (code "27") (name "Net-(EPD_C5-Pad1)") (class "Default")
      (node (ref "EPD_C5") (pin "1") (pinfunction "1_1") (pintype "passive"))
      (node (ref "J1") (pin "15") (pinfunction "15_15") (pintype "bidirectional"))
    )
    (net (code "28") (name "Net-(EPD_C6-Pad1)") (class "Default")
      (node (ref "EPD_C6") (pin "1") (pinfunction "1_1") (pintype "passive"))
      (node (ref "J1") (pin "18") (pinfunction "18_18") (pintype "bidirectional"))
    )
    (net (code "29") (name "Net-(EPD_C7-Pad1)") (class "Default")
      (node (ref "EPD_C7") (pin "1") (pinfunction "1_1") (pintype "passive"))
      (node (ref "J1") (pin "19") (pinfunction "19_19") (pintype "bidirectional"))
    )
    (net (code "30") (name "Net-(EPD_C8-Pad1)") (class "Default")
      (node (ref "EPD_C8") (pin "1") (pinfunction "1_1") (pintype "passive"))
      (node (ref "J1") (pin "20") (pinfunction "20_20") (pintype "bidirectional"))
    )
    (net (code "31") (name "Net-(EPD_C10-Pad1)") (class "Default")
      (node (ref "EPD_C10") (pin "1") (pinfunction "1_1") (pintype "passive"))
      (node (ref "J1") (pin "22") (pinfunction "22_22") (pintype "bidirectional"))
    )
    (net (code "32") (name "Net-(EPD_C12-Pad1)") (class "Default")
      (node (ref "EPD_C12") (pin "1") (pinfunction "1_1") (pintype "passive"))
      (node (ref "J1") (pin "24") (pinfunction "24_24") (pintype "bidirectional"))
    )
    (net (code "33") (name "Net-(IC1-CT)") (class "Default")
      (node (ref "C_DELAY") (pin "1") (pinfunction "1_1") (pintype "passive"))
      (node (ref "IC1") (pin "5") (pinfunction "CT_5") (pintype "bidirectional"))
    )
    (net (code "34") (name "Net-(J2-PadA5)") (class "Default")
      (node (ref "J2") (pin "A5") (pinfunction "A5_A5") (pintype "bidirectional"))
      (node (ref "R2-USB1") (pin "2") (pinfunction "2_2") (pintype "passive"))
    )
    (net (code "35") (name "Net-(J2-PadB5)") (class "Default")
      (node (ref "J2") (pin "B5") (pinfunction "B5_B5") (pintype "bidirectional"))
      (node (ref "R2-USB") (pin "1") (pinfunction "1_1") (pintype "passive"))
    )
    (net (code "36") (name "Net-(MCP73831-PROG)") (class "Default")
      (node (ref "MCP73831") (pin "5") (pinfunction "PROG_5") (pintype "input"))
      (node (ref "R2_BAT") (pin "2") (pinfunction "2_2") (pintype "passive"))
    )
    (net (code "37") (name "Net-(MCP73831-STAT)") (class "Default")
      (node (ref "MCP73831") (pin "1") (pinfunction "STAT_1") (pintype "output"))
      (node (ref "R1_BAT") (pin "1") (pinfunction "1_1") (pintype "passive"))
    )
    (net (code "38") (name "PREVGH") (class "Default")
      (node (ref "D5") (pin "2") (pinfunction "K_2") (pintype "bidirectional"))
      (node (ref "EPD_C9") (pin "1") (pinfunction "1_1") (pintype "passive"))
      (node (ref "J1") (pin "21") (pinfunction "21_21") (pintype "bidirectional"))
    )
    (net (code "39") (name "PREVGL") (class "Default")
      (node (ref "D4") (pin "1") (pinfunction "A_1") (pintype "bidirectional"))
      (node (ref "EPD_C11") (pin "1") (pinfunction "1_1") (pintype "passive"))
      (node (ref "J1") (pin "23") (pinfunction "23_23") (pintype "bidirectional"))
    )
    (net (code "40") (name "RESE") (class "Default")
      (node (ref "J1") (pin "3") (pinfunction "3_3") (pintype "bidirectional"))
      (node (ref "Q3") (pin "2") (pinfunction "S_2") (pintype "bidirectional"))
      (node (ref "R3") (pin "1") (pinfunction "1_1") (pintype "passive"))
    )
    (net (code "41") (name "RESE'") (class "Default")
      (node (ref "R2") (pin "2") (pinfunction "2_2") (pintype "passive"))
      (node (ref "R3") (pin "2") (pinfunction "2_2") (pintype "passive"))
      (node (ref "SJ1") (pin "2") (pinfunction "2_2") (pintype "passive"))
    )
    (net (code "42") (name "RESET") (class "Default")
      (node (ref "C5") (pin "1") (pinfunction "1_1") (pintype "passive"))
      (node (ref "IC1") (pin "1") (pinfunction "VOUT_1") (pintype "bidirectional"))
      (node (ref "RESET_BUTTON") (pin "3") (pinfunction "3_3") (pintype "passive"))
      (node (ref "RESET_BUTTON") (pin "4") (pinfunction "4_4") (pintype "passive"))
      (node (ref "R_RESET") (pin "2") (pinfunction "2_2") (pintype "passive"))
      (node (ref "U2") (pin "3") (pinfunction "EN_3") (pintype "input"))
    )
    (net (code "43") (name "RTC_RST") (class "Default")
      (node (ref "U2") (pin "16") (pinfunction "IO18_16") (pintype "bidirectional"))
      (node (ref "U3") (pin "4") (pinfunction "~{RST}_4") (pintype "input"))
    )
    (net (code "44") (name "RX") (class "Default")
      (node (ref "TP2") (pin "TP") (pinfunction "TP_TP") (pintype "input"))
      (node (ref "U2") (pin "24") (pinfunction "RXD0/GPIO17_24") (pintype "bidirectional"))
    )
    (net (code "45") (name "SCK") (class "Default")
      (node (ref "D10") (pin "2") (pinfunction "2_2") (pintype "passive"))
      (node (ref "J1") (pin "13") (pinfunction "13_13") (pintype "bidirectional"))
      (node (ref "J4") (pin "P5") (pinfunction "CLK_P5") (pintype "bidirectional"))
      (node (ref "R6") (pin "1") (pinfunction "1_1") (pintype "passive"))
      (node (ref "TP8") (pin "TP") (pinfunction "TP_TP") (pintype "input"))
      (node (ref "U1") (pin "6") (pinfunction "CLK_6") (pintype "input"))
      (node (ref "U2") (pin "6") (pinfunction "IO6_6") (pintype "bidirectional"))
    )
    (net (code "46") (name "SCL") (class "Default")
      (node (ref "J3") (pin "4") (pinfunction "4_4") (pintype "passive"))
      (node (ref "R2-PINH") (pin "1") (pinfunction "1_1") (pintype "passive"))
      (node (ref "SENSOR2") (pin "4") (pinfunction "SCK_4") (pintype "input"))
      (node (ref "U2") (pin "20") (pinfunction "IO22_20") (pintype "bidirectional"))
      (node (ref "U3") (pin "16") (pinfunction "SCL_16") (pintype "input"))
      (node (ref "U4") (pin "7") (pinfunction "SCL_7") (pintype "input"))
    )
    (net (code "47") (name "SDA") (class "Default")
      (node (ref "J3") (pin "3") (pinfunction "3_3") (pintype "passive"))
      (node (ref "R1-PINH") (pin "1") (pinfunction "1_1") (pintype "passive"))
      (node (ref "SENSOR2") (pin "3") (pinfunction "SDI_3") (pintype "bidirectional"))
      (node (ref "U2") (pin "19") (pinfunction "IO21_19") (pintype "bidirectional"))
      (node (ref "U3") (pin "15") (pinfunction "SDA_15") (pintype "bidirectional"))
      (node (ref "U4") (pin "8") (pinfunction "SDA_8") (pintype "bidirectional"))
    )
    (net (code "48") (name "SRC") (class "Default")
      (node (ref "C4") (pin "2") (pinfunction "2_2") (pintype "passive"))
      (node (ref "D5") (pin "1") (pinfunction "A_1") (pintype "bidirectional"))
      (node (ref "L1") (pin "1") (pinfunction "1_1") (pintype "passive"))
      (node (ref "Q3") (pin "3") (pinfunction "D_3") (pintype "bidirectional"))
    )
    (net (code "49") (name "SS_SD") (class "Default")
      (node (ref "D8") (pin "2") (pinfunction "2_2") (pintype "passive"))
      (node (ref "J4") (pin "P2") (pinfunction "CD/DAT3_P2") (pintype "bidirectional"))
      (node (ref "R10") (pin "1") (pinfunction "1_1") (pintype "passive"))
      (node (ref "U2") (pin "4") (pinfunction "IO4_4") (pintype "bidirectional"))
    )
    (net (code "50") (name "TX") (class "Default")
      (node (ref "TP1") (pin "TP") (pinfunction "TP_TP") (pintype "input"))
      (node (ref "U2") (pin "25") (pinfunction "TXD0/GPIO16_25") (pintype "bidirectional"))
    )
    (net (code "51") (name "USB_D+") (class "Default")
      (node (ref "D1") (pin "1") (pinfunction "I/O1_1_1") (pintype "bidirectional"))
      (node (ref "U2") (pin "14") (pinfunction "IO13_14") (pintype "bidirectional"))
    )
    (net (code "52") (name "USB_D-") (class "Default")
      (node (ref "D1") (pin "3") (pinfunction "I/O2_1_3") (pintype "bidirectional"))
      (node (ref "U2") (pin "13") (pinfunction "IO12_13") (pintype "bidirectional"))
    )
    (net (code "53") (name "VBAT") (class "Default")
      (node (ref "C2_BAT") (pin "1") (pinfunction "1_1") (pintype "passive"))
      (node (ref "MCP73831") (pin "3") (pinfunction "VBAT_3") (pintype "power_in"))
      (node (ref "Q1") (pin "1") (pinfunction "D_1") (pintype "bidirectional"))
      (node (ref "TP3") (pin "TP") (pinfunction "TP_TP") (pintype "input"))
      (node (ref "U4") (pin "2") (pinfunction "CELL_2") (pintype "power_in"))
      (node (ref "U4") (pin "3") (pinfunction "VDD_3") (pintype "power_in"))
    )
    (net (code "54") (name "VBUS") (class "Default")
      (node (ref "C1_BAT") (pin "1") (pinfunction "1_1") (pintype "passive"))
      (node (ref "C4_USB") (pin "1") (pinfunction "1_1") (pintype "passive"))
      (node (ref "C5_USB") (pin "1") (pinfunction "1_1") (pintype "passive"))
      (node (ref "CHG_LED") (pin "A") (pinfunction "A_A") (pintype "passive"))
      (node (ref "D1") (pin "5") (pinfunction "VBUS_5") (pintype "bidirectional"))
      (node (ref "D2") (pin "1") (pinfunction "ANODE_1") (pintype "bidirectional"))
      (node (ref "MCP73831") (pin "4") (pinfunction "VIN_4") (pintype "power_in"))
      (node (ref "PFMF.050.1") (pin "2") (pinfunction "2_2") (pintype "passive"))
      (node (ref "Q1") (pin "2") (pinfunction "G_2") (pintype "bidirectional"))
      (node (ref "R1_PWRUSB") (pin "2") (pinfunction "2_2") (pintype "passive"))
      (node (ref "TP14") (pin "TP") (pinfunction "TP_TP") (pintype "input"))
    )
    (net (code "55") (name "VRTC") (class "Default")
      (node (ref "C10_SUPERCAP") (pin "2") (pinfunction "2_2") (pintype "passive"))
      (node (ref "C8") (pin "1") (pinfunction "1_1") (pintype "passive"))
      (node (ref "R_CAPACITOR") (pin "1") (pinfunction "1_1") (pintype "passive"))
      (node (ref "U3") (pin "14") (pinfunction "VBAT_14") (pintype "power_in"))
    )
    (net (code "56") (name "VUSB") (class "Default")
      (node (ref "J2") (pin "A4") (pinfunction "A4_A4") (pintype "bidirectional"))
      (node (ref "J2") (pin "A9") (pinfunction "A9_A9") (pintype "bidirectional"))
      (node (ref "J2") (pin "B4") (pinfunction "B4_B4") (pintype "bidirectional"))
      (node (ref "J2") (pin "B9") (pinfunction "B9_B9") (pintype "bidirectional"))
      (node (ref "PFMF.050.1") (pin "1") (pinfunction "1_1") (pintype "passive"))
    )
    (net (code "57") (name "unconnected-(IC1-NC-Pad4)") (class "Default")
      (node (ref "IC1") (pin "4") (pinfunction "NC_4") (pintype "no_connect"))
    )
    (net (code "58") (name "unconnected-(IC4-NC-Pad4)") (class "Default")
      (node (ref "IC4") (pin "4") (pinfunction "NC_4") (pintype "no_connect"))
    )
    (net (code "59") (name "unconnected-(J1-Pad1)") (class "Default")
      (node (ref "J1") (pin "1") (pinfunction "1_1") (pintype "bidirectional"))
    )
    (net (code "60") (name "unconnected-(J1-Pad6)") (class "Default")
      (node (ref "J1") (pin "6") (pinfunction "6_6") (pintype "bidirectional"))
    )
    (net (code "61") (name "unconnected-(J1-Pad7)") (class "Default")
      (node (ref "J1") (pin "7") (pinfunction "7_7") (pintype "bidirectional"))
    )
    (net (code "62") (name "unconnected-(J2-PadA8)") (class "Default")
      (node (ref "J2") (pin "A8") (pinfunction "A8_A8") (pintype "bidirectional"))
    )
    (net (code "63") (name "unconnected-(J2-PadB8)") (class "Default")
      (node (ref "J2") (pin "B8") (pinfunction "B8_B8") (pintype "bidirectional"))
    )
    (net (code "64") (name "unconnected-(J4-DAT1-PadP8)") (class "Default")
      (node (ref "J4") (pin "P8") (pinfunction "DAT1_P8") (pintype "bidirectional"))
    )
    (net (code "65") (name "unconnected-(J4-DAT2-PadP1)") (class "Default")
      (node (ref "J4") (pin "P1") (pinfunction "DAT2_P1") (pintype "bidirectional"))
    )
    (net (code "66") (name "unconnected-(J4-DETECTION_1-PadS1)") (class "Default")
      (node (ref "J4") (pin "S1") (pinfunction "DETECTION_1_S1") (pintype "bidirectional"))
    )
    (net (code "67") (name "unconnected-(J4-DETECTION_2-PadS2)") (class "Default")
      (node (ref "J4") (pin "S2") (pinfunction "DETECTION_2_S2") (pintype "bidirectional"))
    )
    (net (code "68") (name "unconnected-(U2-NC-Pad22)") (class "Default")
      (node (ref "U2") (pin "22") (pinfunction "NC_22") (pintype "no_connect"))
    )
    (net (code "69") (name "unconnected-(U4-~{ALERT}-Pad5)") (class "Default")
      (node (ref "U4") (pin "5") (pinfunction "~{ALERT}_5") (pintype "output"))
    )
  )
)
